# OBC_Flash.net
KiCad netlist of a schematic drawn in Altium Designer
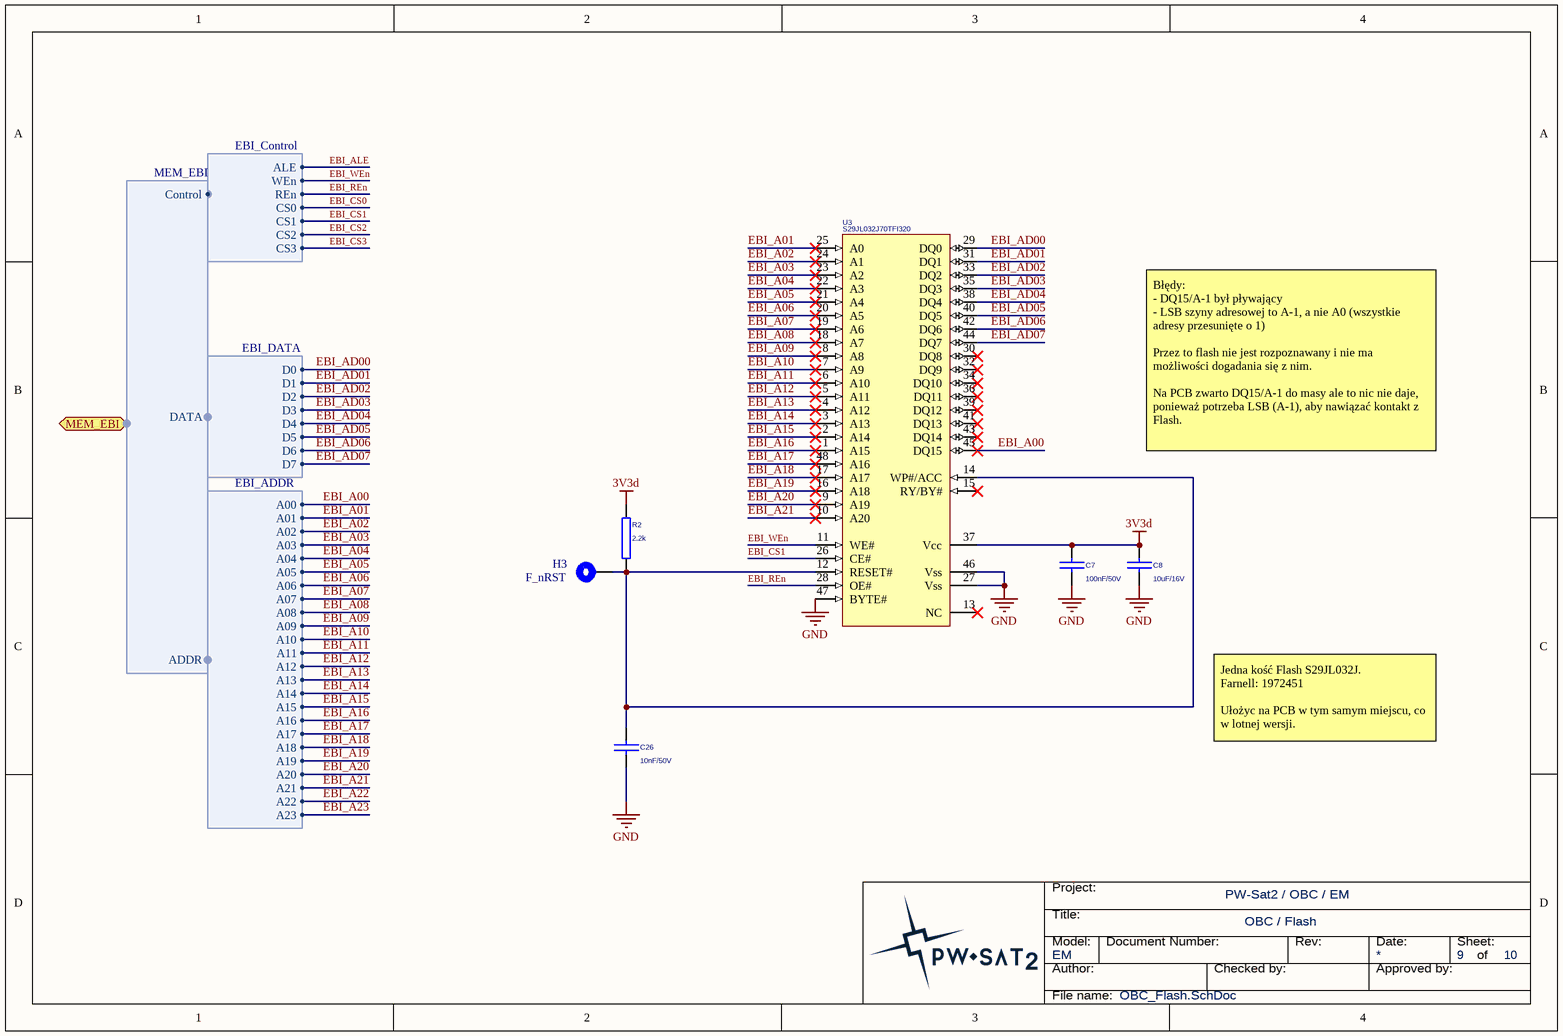
[diagram p0: OBC_Flash.SchDoc]

(export (version "E")
  (design (tool "Eeschema 10.0.6"))
  (components
    (comp (ref "C7")
      (value "100nF/50V")
      (footprint "C0603")
      (description "Capacitator")
      (fields (field (name "VOLTAGE") "50V"))
      (libsource (lib "SchLib") (part "CAP"))
    )
    (comp (ref "C8")
      (value "10uF/16V")
      (footprint "C1206")
      (description "Capacitator")
      (fields (field (name "VOLTAGE") "16V"))
      (libsource (lib "SchLib") (part "CAP"))
    )
    (comp (ref "C26")
      (value "10nF/50V")
      (footprint "C0603")
      (description "Capacitator")
      (fields (field (name "VOLTAGE") "50V"))
      (libsource (lib "SchLib") (part "CAP"))
    )
    (comp (ref "H3")
      (value "F_nRST")
      (footprint "TESTPOINT")
      (description "An AWG-30 wire solder point.")
      (libsource (lib "connectors_printed-circuit-board") (part "Wire_AWG-30"))
    )
    (comp (ref "R2")
      (value "2.2k")
      (footprint "R0603")
      (description "Resistor")
      (fields (field (name "TOLERANCE") "1%"))
      (libsource (lib "SchLib") (part "RES"))
    )
    (comp (ref "U3")
      (value "S29JL032J70TFI320")
      (footprint "TSSOP50P2000X125-48N")
      (description "IC FLASH 32MBIT 70NS 48TSOP")
      (fields (field (name "MANUFACTURER") "Cypress Semiconductor"))
      (libsource (lib "OBC") (part "S29JL032J"))
    )
  )
  (nets
    (net (code "2") (name "/EBI_A00") (class "Default")
      (node (ref "U3") (pin "45") (pinfunction "DQ15_45") (pintype "bidirectional+no_connect"))
    )
    (net (code "3") (name "/EBI_A01") (class "Default")
      (node (ref "U3") (pin "25") (pinfunction "A0_25") (pintype "input+no_connect"))
    )
    (net (code "4") (name "/EBI_A02") (class "Default")
      (node (ref "U3") (pin "24") (pinfunction "A1_24") (pintype "input+no_connect"))
    )
    (net (code "5") (name "/EBI_A03") (class "Default")
      (node (ref "U3") (pin "23") (pinfunction "A2_23") (pintype "input+no_connect"))
    )
    (net (code "6") (name "/EBI_A04") (class "Default")
      (node (ref "U3") (pin "22") (pinfunction "A3_22") (pintype "input+no_connect"))
    )
    (net (code "7") (name "/EBI_A05") (class "Default")
      (node (ref "U3") (pin "21") (pinfunction "A4_21") (pintype "input+no_connect"))
    )
    (net (code "8") (name "/EBI_A06") (class "Default")
      (node (ref "U3") (pin "20") (pinfunction "A5_20") (pintype "input+no_connect"))
    )
    (net (code "9") (name "/EBI_A07") (class "Default")
      (node (ref "U3") (pin "19") (pinfunction "A6_19") (pintype "input+no_connect"))
    )
    (net (code "10") (name "/EBI_A08") (class "Default")
      (node (ref "U3") (pin "18") (pinfunction "A7_18") (pintype "input+no_connect"))
    )
    (net (code "11") (name "/EBI_A09") (class "Default")
      (node (ref "U3") (pin "8") (pinfunction "A8_8") (pintype "input+no_connect"))
    )
    (net (code "12") (name "/EBI_A10") (class "Default")
      (node (ref "U3") (pin "7") (pinfunction "A9_7") (pintype "input+no_connect"))
    )
    (net (code "13") (name "/EBI_A11") (class "Default")
      (node (ref "U3") (pin "6") (pinfunction "A10_6") (pintype "input+no_connect"))
    )
    (net (code "14") (name "/EBI_A12") (class "Default")
      (node (ref "U3") (pin "5") (pinfunction "A11_5") (pintype "input+no_connect"))
    )
    (net (code "15") (name "/EBI_A13") (class "Default")
      (node (ref "U3") (pin "4") (pinfunction "A12_4") (pintype "input+no_connect"))
    )
    (net (code "16") (name "/EBI_A14") (class "Default")
      (node (ref "U3") (pin "3") (pinfunction "A13_3") (pintype "input+no_connect"))
    )
    (net (code "17") (name "/EBI_A15") (class "Default")
      (node (ref "U3") (pin "2") (pinfunction "A14_2") (pintype "input+no_connect"))
    )
    (net (code "18") (name "/EBI_A16") (class "Default")
      (node (ref "U3") (pin "1") (pinfunction "A15_1") (pintype "input+no_connect"))
    )
    (net (code "19") (name "/EBI_A17") (class "Default")
      (node (ref "U3") (pin "48") (pinfunction "A16_48") (pintype "input+no_connect"))
    )
    (net (code "20") (name "/EBI_A18") (class "Default")
      (node (ref "U3") (pin "17") (pinfunction "A17_17") (pintype "input+no_connect"))
    )
    (net (code "21") (name "/EBI_A19") (class "Default")
      (node (ref "U3") (pin "16") (pinfunction "A18_16") (pintype "input+no_connect"))
    )
    (net (code "22") (name "/EBI_A20") (class "Default")
      (node (ref "U3") (pin "9") (pinfunction "A19_9") (pintype "input+no_connect"))
    )
    (net (code "23") (name "/EBI_A21") (class "Default")
      (node (ref "U3") (pin "10") (pinfunction "A20_10") (pintype "input+no_connect"))
    )
    (net (code "26") (name "/EBI_AD00") (class "Default")
      (node (ref "U3") (pin "29") (pinfunction "DQ0_29") (pintype "bidirectional"))
    )
    (net (code "27") (name "/EBI_AD01") (class "Default")
      (node (ref "U3") (pin "31") (pinfunction "DQ1_31") (pintype "bidirectional"))
    )
    (net (code "28") (name "/EBI_AD02") (class "Default")
      (node (ref "U3") (pin "33") (pinfunction "DQ2_33") (pintype "bidirectional"))
    )
    (net (code "29") (name "/EBI_AD03") (class "Default")
      (node (ref "U3") (pin "35") (pinfunction "DQ3_35") (pintype "bidirectional"))
    )
    (net (code "30") (name "/EBI_AD04") (class "Default")
      (node (ref "U3") (pin "38") (pinfunction "DQ4_38") (pintype "bidirectional"))
    )
    (net (code "31") (name "/EBI_AD05") (class "Default")
      (node (ref "U3") (pin "40") (pinfunction "DQ5_40") (pintype "bidirectional"))
    )
    (net (code "32") (name "/EBI_AD06") (class "Default")
      (node (ref "U3") (pin "42") (pinfunction "DQ6_42") (pintype "bidirectional"))
    )
    (net (code "33") (name "/EBI_AD07") (class "Default")
      (node (ref "U3") (pin "44") (pinfunction "DQ7_44") (pintype "bidirectional"))
    )
    (net (code "36") (name "/EBI_CS1") (class "Default")
      (node (ref "U3") (pin "26") (pinfunction "CE#_26") (pintype "input"))
    )
    (net (code "39") (name "/EBI_REn") (class "Default")
      (node (ref "U3") (pin "28") (pinfunction "OE#_28") (pintype "input"))
    )
    (net (code "40") (name "/EBI_WEn") (class "Default")
      (node (ref "U3") (pin "11") (pinfunction "WE#_11") (pintype "input"))
    )
    (net (code "42") (name "3V3d") (class "Default")
      (node (ref "C7") (pin "1") (pintype "passive"))
      (node (ref "C8") (pin "1") (pintype "passive"))
      (node (ref "R2") (pin "2") (pintype "passive"))
      (node (ref "U3") (pin "37") (pinfunction "Vcc_37") (pintype "passive"))
    )
    (net (code "43") (name "GND") (class "Default")
      (node (ref "C26") (pin "2") (pintype "passive"))
      (node (ref "C7") (pin "2") (pintype "passive"))
      (node (ref "C8") (pin "2") (pintype "passive"))
      (node (ref "U3") (pin "27") (pinfunction "Vss_27") (pintype "passive"))
      (node (ref "U3") (pin "46") (pinfunction "Vss_46") (pintype "passive"))
      (node (ref "U3") (pin "47") (pinfunction "BYTE#_47") (pintype "input"))
    )
    (net (code "44") (name "Net-(U3-RESET#)") (class "Default")
      (node (ref "C26") (pin "1") (pintype "passive"))
      (node (ref "H3") (pin "1") (pinfunction "1_1") (pintype "passive"))
      (node (ref "R2") (pin "1") (pintype "passive"))
      (node (ref "U3") (pin "12") (pinfunction "RESET#_12") (pintype "input"))
      (node (ref "U3") (pin "14") (pinfunction "WP#/ACC_14") (pintype "input"))
    )
    (net (code "45") (name "unconnected-(U3-DQ8-Pad30)") (class "Default")
      (node (ref "U3") (pin "30") (pinfunction "DQ8_30") (pintype "bidirectional+no_connect"))
    )
    (net (code "46") (name "unconnected-(U3-DQ9-Pad32)") (class "Default")
      (node (ref "U3") (pin "32") (pinfunction "DQ9_32") (pintype "bidirectional+no_connect"))
    )
    (net (code "47") (name "unconnected-(U3-DQ10-Pad34)") (class "Default")
      (node (ref "U3") (pin "34") (pinfunction "DQ10_34") (pintype "bidirectional+no_connect"))
    )
    (net (code "48") (name "unconnected-(U3-DQ11-Pad36)") (class "Default")
      (node (ref "U3") (pin "36") (pinfunction "DQ11_36") (pintype "bidirectional+no_connect"))
    )
    (net (code "49") (name "unconnected-(U3-DQ12-Pad39)") (class "Default")
      (node (ref "U3") (pin "39") (pinfunction "DQ12_39") (pintype "bidirectional+no_connect"))
    )
    (net (code "50") (name "unconnected-(U3-DQ13-Pad41)") (class "Default")
      (node (ref "U3") (pin "41") (pinfunction "DQ13_41") (pintype "bidirectional+no_connect"))
    )
    (net (code "51") (name "unconnected-(U3-DQ14-Pad43)") (class "Default")
      (node (ref "U3") (pin "43") (pinfunction "DQ14_43") (pintype "bidirectional+no_connect"))
    )
    (net (code "52") (name "unconnected-(U3-NC-Pad13)") (class "Default")
      (node (ref "U3") (pin "13") (pinfunction "NC_13") (pintype "passive+no_connect"))
    )
    (net (code "53") (name "unconnected-(U3-RY{slash}BY#-Pad15)") (class "Default")
      (node (ref "U3") (pin "15") (pinfunction "RY/BY#_15") (pintype "input+no_connect"))
    )
  )
)
